# Lab5_prelab1.net
KiCad netlist of a schematic drawn in Altium Designer
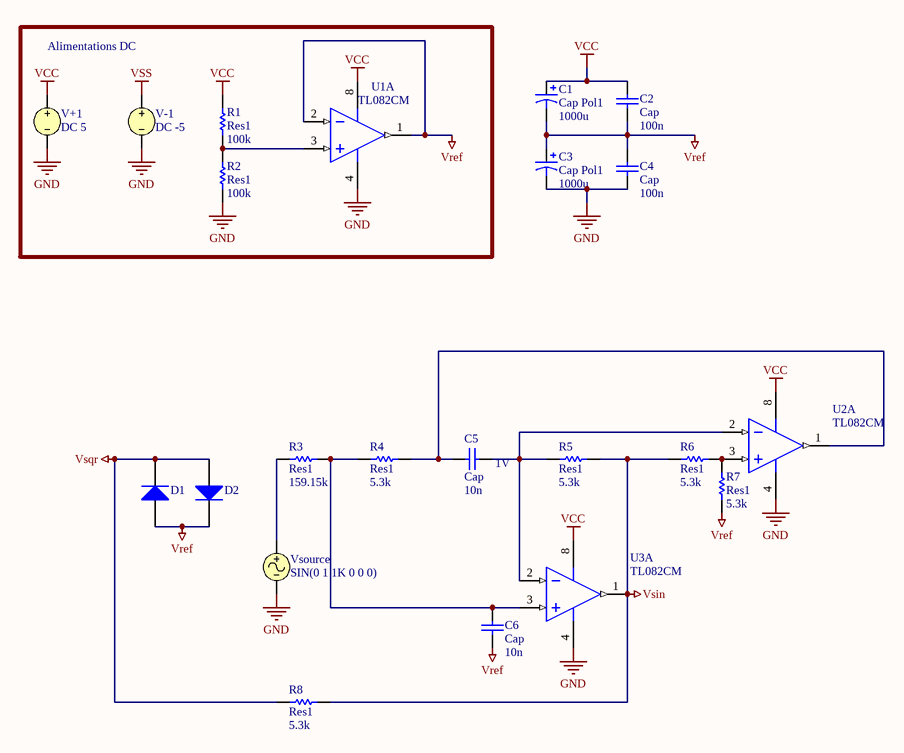
[diagram p0: Lab5_prelab1.SchDoc]

(export (version "E")
  (design (tool "Eeschema 10.0.6"))
  (components
    (comp (ref "C1")
      (value "Cap Pol1")
      (footprint "RB7.6-15")
      (description "Polarized Capacitor (Radial)")
      (fields (field (name "ALTIUM_VALUE") "1000u") (field (name "PUBLISHER") "Altium Limited"))
      (libsource (lib "Miscellaneous Devices") (part "Cap Pol1"))
    )
    (comp (ref "C2")
      (value "Cap")
      (footprint "RAD-0.3")
      (description "Capacitor")
      (fields (field (name "ALTIUM_VALUE") "100n") (field (name "PUBLISHER") "Altium Limited"))
      (libsource (lib "Miscellaneous Devices") (part "Cap"))
    )
    (comp (ref "C3")
      (value "Cap Pol1")
      (footprint "RB7.6-15")
      (description "Polarized Capacitor (Radial)")
      (fields (field (name "ALTIUM_VALUE") "1000u") (field (name "PUBLISHER") "Altium Limited"))
      (libsource (lib "Miscellaneous Devices") (part "Cap Pol1"))
    )
    (comp (ref "C4")
      (value "Cap")
      (footprint "RAD-0.3")
      (description "Capacitor")
      (fields (field (name "ALTIUM_VALUE") "100n") (field (name "PUBLISHER") "Altium Limited"))
      (libsource (lib "Miscellaneous Devices") (part "Cap"))
    )
    (comp (ref "C5")
      (value "Cap")
      (footprint "RAD-0.3")
      (description "Capacitor")
      (fields
        (field (name "ALTIUM_VALUE") "10n")
        (field (name "INITIAL VOLTAGE") "1V")
        (field (name "PUBLISHER") "Altium Limited")
      )
      (libsource (lib "Miscellaneous Devices") (part "Cap"))
    )
    (comp (ref "C6")
      (value "Cap")
      (footprint "RAD-0.3")
      (description "Capacitor")
      (fields (field (name "ALTIUM_VALUE") "10n") (field (name "PUBLISHER") "Altium Limited"))
      (libsource (lib "Miscellaneous Devices") (part "Cap"))
    )
    (comp (ref "D1")
      (value "Diode 1N4148")
      (footprint "DO-35")
      (description "High Conductance Fast Diode")
      (fields (field (name "PUBLISHER") "Altium Limited"))
      (libsource (lib "Miscellaneous Devices") (part "Diode 1N4148"))
    )
    (comp (ref "D2")
      (value "Diode 1N4148")
      (footprint "DO-35")
      (description "High Conductance Fast Diode")
      (fields (field (name "PUBLISHER") "Altium Limited"))
      (libsource (lib "Miscellaneous Devices") (part "Diode 1N4148"))
    )
    (comp (ref "R1")
      (value "Res1")
      (footprint "AXIAL-0.3")
      (description "Resistor")
      (fields (field (name "ALTIUM_VALUE") "100k") (field (name "PUBLISHER") "Altium Limited"))
      (libsource (lib "Miscellaneous Devices") (part "Res1"))
    )
    (comp (ref "R2")
      (value "Res1")
      (footprint "AXIAL-0.3")
      (description "Resistor")
      (fields (field (name "ALTIUM_VALUE") "100k") (field (name "PUBLISHER") "Altium Limited"))
      (libsource (lib "Miscellaneous Devices") (part "Res1"))
    )
    (comp (ref "R3")
      (value "Res1")
      (footprint "AXIAL-0.3")
      (description "Resistor")
      (fields (field (name "ALTIUM_VALUE") "159.15k") (field (name "PUBLISHER") "Altium Limited"))
      (libsource (lib "Miscellaneous Devices") (part "Res1"))
    )
    (comp (ref "R4")
      (value "Res1")
      (footprint "AXIAL-0.3")
      (description "Resistor")
      (fields (field (name "ALTIUM_VALUE") "5.3k") (field (name "PUBLISHER") "Altium Limited"))
      (libsource (lib "Miscellaneous Devices") (part "Res1"))
    )
    (comp (ref "R5")
      (value "Res1")
      (footprint "AXIAL-0.3")
      (description "Resistor")
      (fields (field (name "ALTIUM_VALUE") "5.3k") (field (name "PUBLISHER") "Altium Limited"))
      (libsource (lib "Miscellaneous Devices") (part "Res1"))
    )
    (comp (ref "R6")
      (value "Res1")
      (footprint "AXIAL-0.3")
      (description "Resistor")
      (fields (field (name "ALTIUM_VALUE") "5.3k") (field (name "PUBLISHER") "Altium Limited"))
      (libsource (lib "Miscellaneous Devices") (part "Res1"))
    )
    (comp (ref "R7")
      (value "Res1")
      (footprint "AXIAL-0.3")
      (description "Resistor")
      (fields (field (name "ALTIUM_VALUE") "5.3k") (field (name "PUBLISHER") "Altium Limited"))
      (libsource (lib "Miscellaneous Devices") (part "Res1"))
    )
    (comp (ref "R8")
      (value "Res1")
      (footprint "AXIAL-0.3")
      (description "Resistor")
      (fields (field (name "ALTIUM_VALUE") "5.3k") (field (name "PUBLISHER") "Altium Limited"))
      (libsource (lib "Miscellaneous Devices") (part "Res1"))
    )
    (comp (ref "U1")
      (value "TL082CM")
      (footprint "M08A_N")
      (description "Wide Bandwidth Dual JFET Input Operational Amplifier")
      (fields
        (field (name "MANUFACTURER") "National Semiconductor")
        (field (name "DIGIKEYPARTNUMBER") "TL082CM-ND")
        (field (name "PUBLISHER") "Altium Limited")
      )
      (libsource (lib "NSC Amplifier") (part "TL082CM"))
    )
    (comp (ref "U2")
      (value "TL082CM")
      (footprint "M08A_N")
      (description "Wide Bandwidth Dual JFET Input Operational Amplifier")
      (fields
        (field (name "MANUFACTURER") "National Semiconductor")
        (field (name "DIGIKEYPARTNUMBER") "TL082CM-ND")
        (field (name "PUBLISHER") "Altium Limited")
      )
      (libsource (lib "NSC Amplifier") (part "TL082CM"))
    )
    (comp (ref "U3")
      (value "TL082CM")
      (footprint "M08A_N")
      (description "Wide Bandwidth Dual JFET Input Operational Amplifier")
      (fields
        (field (name "MANUFACTURER") "National Semiconductor")
        (field (name "DIGIKEYPARTNUMBER") "TL082CM-ND")
        (field (name "PUBLISHER") "Altium Limited")
      )
      (libsource (lib "NSC Amplifier") (part "TL082CM"))
    )
    (comp (ref "V+1")
      (value "DC 5")
      (description "Voltage Source")
      (fields (field (name "PUBLISHER") "Altium Limited"))
      (libsource (lib "Simulation Sources") (part "VSRC"))
    )
    (comp (ref "V-1")
      (value "DC -5")
      (description "Voltage Source")
      (fields (field (name "PUBLISHER") "Altium Limited"))
      (libsource (lib "Simulation Sources") (part "VSRC"))
    )
    (comp (ref "Vsource")
      (value "SIN(0 1 1K 0 0 0)")
      (description "Sinusoidal Voltage Source")
      (fields (field (name "PUBLISHER") "Altium Limited"))
      (libsource (lib "Simulation Sources") (part "VSIN"))
    )
  )
  (nets
    (net (code "1") (name "GND") (class "Default")
      (node (ref "C3") (pin "2") (pinfunction "2_2") (pintype "passive"))
      (node (ref "C4") (pin "1") (pinfunction "1_1") (pintype "passive"))
      (node (ref "R2") (pin "1") (pinfunction "1_1") (pintype "passive"))
      (node (ref "U1") (pin "4") (pinfunction "V-_4") (pintype "power_in"))
      (node (ref "U2") (pin "4") (pinfunction "V-_4") (pintype "power_in"))
      (node (ref "U3") (pin "4") (pinfunction "V-_4") (pintype "power_in"))
      (node (ref "V+1") (pin "2") (pinfunction "2_2") (pintype "passive"))
      (node (ref "V-1") (pin "2") (pinfunction "2_2") (pintype "passive"))
      (node (ref "Vsource") (pin "2") (pinfunction "2_2") (pintype "passive"))
    )
    (net (code "2") (name "Net-(R3-Pad1)") (class "Default")
      (node (ref "R3") (pin "1") (pinfunction "1_1") (pintype "passive"))
      (node (ref "Vsource") (pin "1") (pinfunction "1_1") (pintype "passive"))
    )
    (net (code "3") (name "Net-(U1A-INA+)") (class "Default")
      (node (ref "R1") (pin "1") (pinfunction "1_1") (pintype "passive"))
      (node (ref "R2") (pin "2") (pinfunction "2_2") (pintype "passive"))
      (node (ref "U1") (pin "3") (pinfunction "INA+_3") (pintype "input"))
    )
    (net (code "4") (name "Net-(U2A-INA+)") (class "Default")
      (node (ref "R6") (pin "1") (pinfunction "1_1") (pintype "passive"))
      (node (ref "R7") (pin "2") (pinfunction "2_2") (pintype "passive"))
      (node (ref "U2") (pin "3") (pinfunction "INA+_3") (pintype "input"))
    )
    (net (code "5") (name "Net-(U2A-INA-)") (class "Default")
      (node (ref "C5") (pin "2") (pinfunction "2_2") (pintype "passive"))
      (node (ref "R5") (pin "2") (pinfunction "2_2") (pintype "passive"))
      (node (ref "U2") (pin "2") (pinfunction "INA-_2") (pintype "input"))
      (node (ref "U3") (pin "2") (pinfunction "INA-_2") (pintype "input"))
    )
    (net (code "6") (name "Net-(U2A-OUTA)") (class "Default")
      (node (ref "C5") (pin "1") (pinfunction "1_1") (pintype "passive"))
      (node (ref "R4") (pin "2") (pinfunction "2_2") (pintype "passive"))
      (node (ref "U2") (pin "1") (pinfunction "OUTA_1") (pintype "output"))
    )
    (net (code "7") (name "Net-(U3A-INA+)") (class "Default")
      (node (ref "C6") (pin "2") (pinfunction "2_2") (pintype "passive"))
      (node (ref "R3") (pin "2") (pinfunction "2_2") (pintype "passive"))
      (node (ref "R4") (pin "1") (pinfunction "1_1") (pintype "passive"))
      (node (ref "U3") (pin "3") (pinfunction "INA+_3") (pintype "input"))
    )
    (net (code "8") (name "VCC") (class "Default")
      (node (ref "C1") (pin "1") (pinfunction "1_1") (pintype "passive"))
      (node (ref "C2") (pin "2") (pinfunction "2_2") (pintype "passive"))
      (node (ref "R1") (pin "2") (pinfunction "2_2") (pintype "passive"))
      (node (ref "U1") (pin "8") (pinfunction "V+_8") (pintype "power_in"))
      (node (ref "U2") (pin "8") (pinfunction "V+_8") (pintype "power_in"))
      (node (ref "U3") (pin "8") (pinfunction "V+_8") (pintype "power_in"))
      (node (ref "V+1") (pin "1") (pinfunction "1_1") (pintype "passive"))
    )
    (net (code "9") (name "VSS") (class "Default")
      (node (ref "V-1") (pin "1") (pinfunction "1_1") (pintype "passive"))
    )
    (net (code "10") (name "Vref") (class "Default")
      (node (ref "C1") (pin "2") (pinfunction "2_2") (pintype "passive"))
      (node (ref "C2") (pin "1") (pinfunction "1_1") (pintype "passive"))
      (node (ref "C3") (pin "1") (pinfunction "1_1") (pintype "passive"))
      (node (ref "C4") (pin "2") (pinfunction "2_2") (pintype "passive"))
      (node (ref "C6") (pin "1") (pinfunction "1_1") (pintype "passive"))
      (node (ref "D1") (pin "1") (pinfunction "A_1") (pintype "passive"))
      (node (ref "D2") (pin "2") (pinfunction "K_2") (pintype "passive"))
      (node (ref "R7") (pin "1") (pinfunction "1_1") (pintype "passive"))
      (node (ref "U1") (pin "1") (pinfunction "OUTA_1") (pintype "output"))
      (node (ref "U1") (pin "2") (pinfunction "INA-_2") (pintype "input"))
    )
    (net (code "11") (name "Vsin") (class "Default")
      (node (ref "R5") (pin "1") (pinfunction "1_1") (pintype "passive"))
      (node (ref "R6") (pin "2") (pinfunction "2_2") (pintype "passive"))
      (node (ref "R8") (pin "2") (pinfunction "2_2") (pintype "passive"))
      (node (ref "U3") (pin "1") (pinfunction "OUTA_1") (pintype "output"))
    )
    (net (code "12") (name "Vsqr") (class "Default")
      (node (ref "D1") (pin "2") (pinfunction "K_2") (pintype "passive"))
      (node (ref "D2") (pin "1") (pinfunction "A_1") (pintype "passive"))
      (node (ref "R8") (pin "1") (pinfunction "1_1") (pintype "passive"))
    )
  )
)
